# MCU.net
KiCad netlist of a schematic drawn in Altium Designer
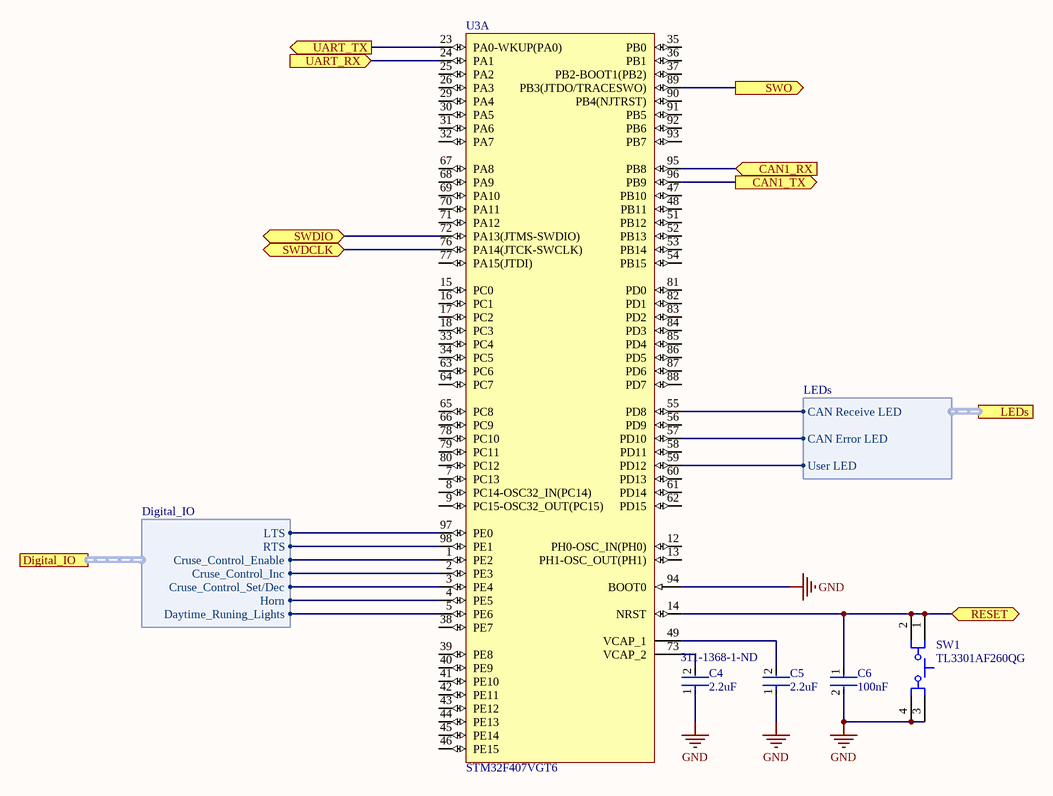
[diagram p0: MCU.SchDoc]

(export (version "E")
  (design (tool "Eeschema 10.0.6"))
  (components
    (comp (ref "C4")
      (value "2.2uF")
      (footprint "Yageo_CC0805-0.85_IPC_A")
      (description "2.2UF CC0805KKX7R6BB225")
      (fields (field (name "SUPPLIER PART NUMBER 1") "311-1368-1-ND") (field (name "TOLERANCE") "10%"))
      (libsource (lib "Cap_Yageo_CC0805KKX7R6BB225_eec") (part "CC0805KKX7R6BB225"))
    )
    (comp (ref "C5")
      (value "2.2uF")
      (footprint "Yageo_CC0805-0.85_IPC_A")
      (description "2.2UF CC0805KKX7R6BB225")
      (libsource (lib "Cap_Yageo_CC0805KKX7R6BB225_eec") (part "CC0805KKX7R6BB225"))
    )
    (comp (ref "C6")
      (value "100nF")
      (footprint "Kemet_C0603_IPC_A")
      (description "CAP CER 0.1UF 100NF 50V X7R 0603 C0603C104K5RACTU")
      (libsource (lib "UNK_Kemet_C0603C104K5RACTU_eec") (part "C0603C104K5RACTU"))
    )
    (comp (ref "SW1")
      (value "TL3301AF260QG")
      (footprint "ESWI-TL3301AF260QG_V")
      (description "Tactile Switch, SPST-NO, 50 mA, 12 V, -20 to 70 degC, 4-Pin SMD, RoHS, Tape and Reel")
      (fields (field (name "MANUFACTURER") "E-Switch"))
      (libsource (lib "Altium Content Vault") (part "SW-SPST-NO-4"))
    )
    (comp (ref "U3")
      (value "STM32F407VGT6")
      (footprint "STM-LQFP100_M")
      (fields (field (name "MANUFACTURER") "STMicroelectronics"))
      (libsource (lib "Altium Content Vault") (part "MC-ARM-STM32F40X_41X-SQ100"))
    )
  )
  (nets
    (net (code "3") (name "/CAN Error LED") (class "Default")
      (node (ref "U3") (pin "57") (pinfunction "PD10_57") (pintype "bidirectional"))
    )
    (net (code "4") (name "/CAN Receive LED") (class "Default")
      (node (ref "U3") (pin "55") (pinfunction "PD8_55") (pintype "bidirectional"))
    )
    (net (code "5") (name "/CAN1_RX") (class "Default")
      (node (ref "U3") (pin "95") (pinfunction "PB8_95") (pintype "bidirectional"))
    )
    (net (code "6") (name "/CAN1_TX") (class "Default")
      (node (ref "U3") (pin "96") (pinfunction "PB9_96") (pintype "bidirectional"))
    )
    (net (code "7") (name "/Cruse_Control_Enable") (class "Default")
      (node (ref "U3") (pin "1") (pinfunction "PE2_1") (pintype "bidirectional"))
    )
    (net (code "8") (name "/Cruse_Control_Inc") (class "Default")
      (node (ref "U3") (pin "2") (pinfunction "PE3_2") (pintype "bidirectional"))
    )
    (net (code "9") (name "/Cruse_Control_Set{slash}Dec") (class "Default")
      (node (ref "U3") (pin "3") (pinfunction "PE4_3") (pintype "bidirectional"))
    )
    (net (code "10") (name "/Daytime_Runing_Lights") (class "Default")
      (node (ref "U3") (pin "5") (pinfunction "PE6_5") (pintype "bidirectional"))
    )
    (net (code "11") (name "/Horn") (class "Default")
      (node (ref "U3") (pin "4") (pinfunction "PE5_4") (pintype "bidirectional"))
    )
    (net (code "12") (name "/LTS") (class "Default")
      (node (ref "U3") (pin "97") (pinfunction "PE0_97") (pintype "bidirectional"))
    )
    (net (code "13") (name "/RESET") (class "Default")
      (node (ref "C6") (pin "1") (pinfunction "1_1") (pintype "passive"))
      (node (ref "SW1") (pin "1") (pinfunction "1_1") (pintype "passive"))
      (node (ref "SW1") (pin "2") (pinfunction "2_2") (pintype "passive"))
      (node (ref "U3") (pin "14") (pinfunction "NRST_14") (pintype "bidirectional"))
    )
    (net (code "14") (name "/RTS") (class "Default")
      (node (ref "U3") (pin "98") (pinfunction "PE1_98") (pintype "bidirectional"))
    )
    (net (code "15") (name "/SWDCLK") (class "Default")
      (node (ref "U3") (pin "76") (pinfunction "PA14(JTCK-SWCLK)_76") (pintype "bidirectional"))
    )
    (net (code "16") (name "/SWDIO") (class "Default")
      (node (ref "U3") (pin "72") (pinfunction "PA13(JTMS-SWDIO)_72") (pintype "bidirectional"))
    )
    (net (code "17") (name "/SWO") (class "Default")
      (node (ref "U3") (pin "89") (pinfunction "PB3(JTDO/TRACESWO)_89") (pintype "bidirectional"))
    )
    (net (code "18") (name "/UART_RX") (class "Default")
      (node (ref "U3") (pin "24") (pinfunction "PA1_24") (pintype "bidirectional"))
    )
    (net (code "19") (name "/UART_TX") (class "Default")
      (node (ref "U3") (pin "23") (pinfunction "PA0-WKUP(PA0)_23") (pintype "bidirectional"))
    )
    (net (code "20") (name "/User LED") (class "Default")
      (node (ref "U3") (pin "59") (pinfunction "PD12_59") (pintype "bidirectional"))
    )
    (net (code "23") (name "GND") (class "Default")
      (node (ref "C4") (pin "1") (pinfunction "1_1") (pintype "passive"))
      (node (ref "C5") (pin "1") (pinfunction "1_1") (pintype "passive"))
      (node (ref "C6") (pin "2") (pinfunction "2_2") (pintype "passive"))
      (node (ref "SW1") (pin "3") (pinfunction "3_3") (pintype "passive"))
      (node (ref "SW1") (pin "4") (pinfunction "4_4") (pintype "passive"))
      (node (ref "U3") (pin "94") (pinfunction "BOOT0_94") (pintype "input"))
    )
    (net (code "24") (name "Net-(U3A-VCAP_1)") (class "Default")
      (node (ref "C5") (pin "2") (pinfunction "2_2") (pintype "passive"))
      (node (ref "U3") (pin "49") (pinfunction "VCAP_1_49") (pintype "power_in"))
    )
    (net (code "25") (name "Net-(U3A-VCAP_2)") (class "Default")
      (node (ref "C4") (pin "2") (pinfunction "2_2") (pintype "passive"))
      (node (ref "U3") (pin "73") (pinfunction "VCAP_2_73") (pintype "power_in"))
    )
    (net (code "26") (name "unconnected-(U3A-PA2-Pad25)") (class "Default")
      (node (ref "U3") (pin "25") (pinfunction "PA2_25") (pintype "bidirectional"))
    )
    (net (code "27") (name "unconnected-(U3A-PA3-Pad26)") (class "Default")
      (node (ref "U3") (pin "26") (pinfunction "PA3_26") (pintype "bidirectional"))
    )
    (net (code "28") (name "unconnected-(U3A-PA4-Pad29)") (class "Default")
      (node (ref "U3") (pin "29") (pinfunction "PA4_29") (pintype "bidirectional"))
    )
    (net (code "29") (name "unconnected-(U3A-PA5-Pad30)") (class "Default")
      (node (ref "U3") (pin "30") (pinfunction "PA5_30") (pintype "bidirectional"))
    )
    (net (code "30") (name "unconnected-(U3A-PA6-Pad31)") (class "Default")
      (node (ref "U3") (pin "31") (pinfunction "PA6_31") (pintype "bidirectional"))
    )
    (net (code "31") (name "unconnected-(U3A-PA7-Pad32)") (class "Default")
      (node (ref "U3") (pin "32") (pinfunction "PA7_32") (pintype "bidirectional"))
    )
    (net (code "32") (name "unconnected-(U3A-PA8-Pad67)") (class "Default")
      (node (ref "U3") (pin "67") (pinfunction "PA8_67") (pintype "bidirectional"))
    )
    (net (code "33") (name "unconnected-(U3A-PA9-Pad68)") (class "Default")
      (node (ref "U3") (pin "68") (pinfunction "PA9_68") (pintype "bidirectional"))
    )
    (net (code "34") (name "unconnected-(U3A-PA10-Pad69)") (class "Default")
      (node (ref "U3") (pin "69") (pinfunction "PA10_69") (pintype "bidirectional"))
    )
    (net (code "35") (name "unconnected-(U3A-PA11-Pad70)") (class "Default")
      (node (ref "U3") (pin "70") (pinfunction "PA11_70") (pintype "bidirectional"))
    )
    (net (code "36") (name "unconnected-(U3A-PA12-Pad71)") (class "Default")
      (node (ref "U3") (pin "71") (pinfunction "PA12_71") (pintype "bidirectional"))
    )
    (net (code "37") (name "unconnected-(U3A-PA15(JTDI)-Pad77)") (class "Default")
      (node (ref "U3") (pin "77") (pinfunction "PA15(JTDI)_77") (pintype "bidirectional"))
    )
    (net (code "38") (name "unconnected-(U3A-PB0-Pad35)") (class "Default")
      (node (ref "U3") (pin "35") (pinfunction "PB0_35") (pintype "bidirectional"))
    )
    (net (code "39") (name "unconnected-(U3A-PB1-Pad36)") (class "Default")
      (node (ref "U3") (pin "36") (pinfunction "PB1_36") (pintype "bidirectional"))
    )
    (net (code "40") (name "unconnected-(U3A-PB2-BOOT1(PB2)-Pad37)") (class "Default")
      (node (ref "U3") (pin "37") (pinfunction "PB2-BOOT1(PB2)_37") (pintype "bidirectional"))
    )
    (net (code "41") (name "unconnected-(U3A-PB4(NJTRST)-Pad90)") (class "Default")
      (node (ref "U3") (pin "90") (pinfunction "PB4(NJTRST)_90") (pintype "bidirectional"))
    )
    (net (code "42") (name "unconnected-(U3A-PB5-Pad91)") (class "Default")
      (node (ref "U3") (pin "91") (pinfunction "PB5_91") (pintype "bidirectional"))
    )
    (net (code "43") (name "unconnected-(U3A-PB6-Pad92)") (class "Default")
      (node (ref "U3") (pin "92") (pinfunction "PB6_92") (pintype "bidirectional"))
    )
    (net (code "44") (name "unconnected-(U3A-PB7-Pad93)") (class "Default")
      (node (ref "U3") (pin "93") (pinfunction "PB7_93") (pintype "bidirectional"))
    )
    (net (code "45") (name "unconnected-(U3A-PB10-Pad47)") (class "Default")
      (node (ref "U3") (pin "47") (pinfunction "PB10_47") (pintype "bidirectional"))
    )
    (net (code "46") (name "unconnected-(U3A-PB11-Pad48)") (class "Default")
      (node (ref "U3") (pin "48") (pinfunction "PB11_48") (pintype "bidirectional"))
    )
    (net (code "47") (name "unconnected-(U3A-PB12-Pad51)") (class "Default")
      (node (ref "U3") (pin "51") (pinfunction "PB12_51") (pintype "bidirectional"))
    )
    (net (code "48") (name "unconnected-(U3A-PB13-Pad52)") (class "Default")
      (node (ref "U3") (pin "52") (pinfunction "PB13_52") (pintype "bidirectional"))
    )
    (net (code "49") (name "unconnected-(U3A-PB14-Pad53)") (class "Default")
      (node (ref "U3") (pin "53") (pinfunction "PB14_53") (pintype "bidirectional"))
    )
    (net (code "50") (name "unconnected-(U3A-PB15-Pad54)") (class "Default")
      (node (ref "U3") (pin "54") (pinfunction "PB15_54") (pintype "bidirectional"))
    )
    (net (code "51") (name "unconnected-(U3A-PC0-Pad15)") (class "Default")
      (node (ref "U3") (pin "15") (pinfunction "PC0_15") (pintype "bidirectional"))
    )
    (net (code "52") (name "unconnected-(U3A-PC1-Pad16)") (class "Default")
      (node (ref "U3") (pin "16") (pinfunction "PC1_16") (pintype "bidirectional"))
    )
    (net (code "53") (name "unconnected-(U3A-PC2-Pad17)") (class "Default")
      (node (ref "U3") (pin "17") (pinfunction "PC2_17") (pintype "bidirectional"))
    )
    (net (code "54") (name "unconnected-(U3A-PC3-Pad18)") (class "Default")
      (node (ref "U3") (pin "18") (pinfunction "PC3_18") (pintype "bidirectional"))
    )
    (net (code "55") (name "unconnected-(U3A-PC4-Pad33)") (class "Default")
      (node (ref "U3") (pin "33") (pinfunction "PC4_33") (pintype "bidirectional"))
    )
    (net (code "56") (name "unconnected-(U3A-PC5-Pad34)") (class "Default")
      (node (ref "U3") (pin "34") (pinfunction "PC5_34") (pintype "bidirectional"))
    )
    (net (code "57") (name "unconnected-(U3A-PC6-Pad63)") (class "Default")
      (node (ref "U3") (pin "63") (pinfunction "PC6_63") (pintype "bidirectional"))
    )
    (net (code "58") (name "unconnected-(U3A-PC7-Pad64)") (class "Default")
      (node (ref "U3") (pin "64") (pinfunction "PC7_64") (pintype "bidirectional"))
    )
    (net (code "59") (name "unconnected-(U3A-PC8-Pad65)") (class "Default")
      (node (ref "U3") (pin "65") (pinfunction "PC8_65") (pintype "bidirectional"))
    )
    (net (code "60") (name "unconnected-(U3A-PC9-Pad66)") (class "Default")
      (node (ref "U3") (pin "66") (pinfunction "PC9_66") (pintype "bidirectional"))
    )
    (net (code "61") (name "unconnected-(U3A-PC10-Pad78)") (class "Default")
      (node (ref "U3") (pin "78") (pinfunction "PC10_78") (pintype "bidirectional"))
    )
    (net (code "62") (name "unconnected-(U3A-PC11-Pad79)") (class "Default")
      (node (ref "U3") (pin "79") (pinfunction "PC11_79") (pintype "bidirectional"))
    )
    (net (code "63") (name "unconnected-(U3A-PC12-Pad80)") (class "Default")
      (node (ref "U3") (pin "80") (pinfunction "PC12_80") (pintype "bidirectional"))
    )
    (net (code "64") (name "unconnected-(U3A-PC13-Pad7)") (class "Default")
      (node (ref "U3") (pin "7") (pinfunction "PC13_7") (pintype "bidirectional"))
    )
    (net (code "65") (name "unconnected-(U3A-PC14-OSC32_IN(PC14)-Pad8)") (class "Default")
      (node (ref "U3") (pin "8") (pinfunction "PC14-OSC32_IN(PC14)_8") (pintype "bidirectional"))
    )
    (net (code "66") (name "unconnected-(U3A-PC15-OSC32_OUT(PC15)-Pad9)") (class "Default")
      (node (ref "U3") (pin "9") (pinfunction "PC15-OSC32_OUT(PC15)_9") (pintype "bidirectional"))
    )
    (net (code "67") (name "unconnected-(U3A-PD0-Pad81)") (class "Default")
      (node (ref "U3") (pin "81") (pinfunction "PD0_81") (pintype "bidirectional"))
    )
    (net (code "68") (name "unconnected-(U3A-PD1-Pad82)") (class "Default")
      (node (ref "U3") (pin "82") (pinfunction "PD1_82") (pintype "bidirectional"))
    )
    (net (code "69") (name "unconnected-(U3A-PD2-Pad83)") (class "Default")
      (node (ref "U3") (pin "83") (pinfunction "PD2_83") (pintype "bidirectional"))
    )
    (net (code "70") (name "unconnected-(U3A-PD3-Pad84)") (class "Default")
      (node (ref "U3") (pin "84") (pinfunction "PD3_84") (pintype "bidirectional"))
    )
    (net (code "71") (name "unconnected-(U3A-PD4-Pad85)") (class "Default")
      (node (ref "U3") (pin "85") (pinfunction "PD4_85") (pintype "bidirectional"))
    )
    (net (code "72") (name "unconnected-(U3A-PD5-Pad86)") (class "Default")
      (node (ref "U3") (pin "86") (pinfunction "PD5_86") (pintype "bidirectional"))
    )
    (net (code "73") (name "unconnected-(U3A-PD6-Pad87)") (class "Default")
      (node (ref "U3") (pin "87") (pinfunction "PD6_87") (pintype "bidirectional"))
    )
    (net (code "74") (name "unconnected-(U3A-PD7-Pad88)") (class "Default")
      (node (ref "U3") (pin "88") (pinfunction "PD7_88") (pintype "bidirectional"))
    )
    (net (code "75") (name "unconnected-(U3A-PD9-Pad56)") (class "Default")
      (node (ref "U3") (pin "56") (pinfunction "PD9_56") (pintype "bidirectional"))
    )
    (net (code "76") (name "unconnected-(U3A-PD11-Pad58)") (class "Default")
      (node (ref "U3") (pin "58") (pinfunction "PD11_58") (pintype "bidirectional"))
    )
    (net (code "77") (name "unconnected-(U3A-PD13-Pad60)") (class "Default")
      (node (ref "U3") (pin "60") (pinfunction "PD13_60") (pintype "bidirectional"))
    )
    (net (code "78") (name "unconnected-(U3A-PD14-Pad61)") (class "Default")
      (node (ref "U3") (pin "61") (pinfunction "PD14_61") (pintype "bidirectional"))
    )
    (net (code "79") (name "unconnected-(U3A-PD15-Pad62)") (class "Default")
      (node (ref "U3") (pin "62") (pinfunction "PD15_62") (pintype "bidirectional"))
    )
    (net (code "80") (name "unconnected-(U3A-PE7-Pad38)") (class "Default")
      (node (ref "U3") (pin "38") (pinfunction "PE7_38") (pintype "bidirectional"))
    )
    (net (code "81") (name "unconnected-(U3A-PE8-Pad39)") (class "Default")
      (node (ref "U3") (pin "39") (pinfunction "PE8_39") (pintype "bidirectional"))
    )
    (net (code "82") (name "unconnected-(U3A-PE9-Pad40)") (class "Default")
      (node (ref "U3") (pin "40") (pinfunction "PE9_40") (pintype "bidirectional"))
    )
    (net (code "83") (name "unconnected-(U3A-PE10-Pad41)") (class "Default")
      (node (ref "U3") (pin "41") (pinfunction "PE10_41") (pintype "bidirectional"))
    )
    (net (code "84") (name "unconnected-(U3A-PE11-Pad42)") (class "Default")
      (node (ref "U3") (pin "42") (pinfunction "PE11_42") (pintype "bidirectional"))
    )
    (net (code "85") (name "unconnected-(U3A-PE12-Pad43)") (class "Default")
      (node (ref "U3") (pin "43") (pinfunction "PE12_43") (pintype "bidirectional"))
    )
    (net (code "86") (name "unconnected-(U3A-PE13-Pad44)") (class "Default")
      (node (ref "U3") (pin "44") (pinfunction "PE13_44") (pintype "bidirectional"))
    )
    (net (code "87") (name "unconnected-(U3A-PE14-Pad45)") (class "Default")
      (node (ref "U3") (pin "45") (pinfunction "PE14_45") (pintype "bidirectional"))
    )
    (net (code "88") (name "unconnected-(U3A-PE15-Pad46)") (class "Default")
      (node (ref "U3") (pin "46") (pinfunction "PE15_46") (pintype "bidirectional"))
    )
    (net (code "89") (name "unconnected-(U3A-PH0-OSC_IN(PH0)-Pad12)") (class "Default")
      (node (ref "U3") (pin "12") (pinfunction "PH0-OSC_IN(PH0)_12") (pintype "bidirectional"))
    )
    (net (code "90") (name "unconnected-(U3A-PH1-OSC_OUT(PH1)-Pad13)") (class "Default")
      (node (ref "U3") (pin "13") (pinfunction "PH1-OSC_OUT(PH1)_13") (pintype "bidirectional"))
    )
  )
)
